# Motor_Driver_Card.net
KiCad netlist of a schematic drawn in EAGLE
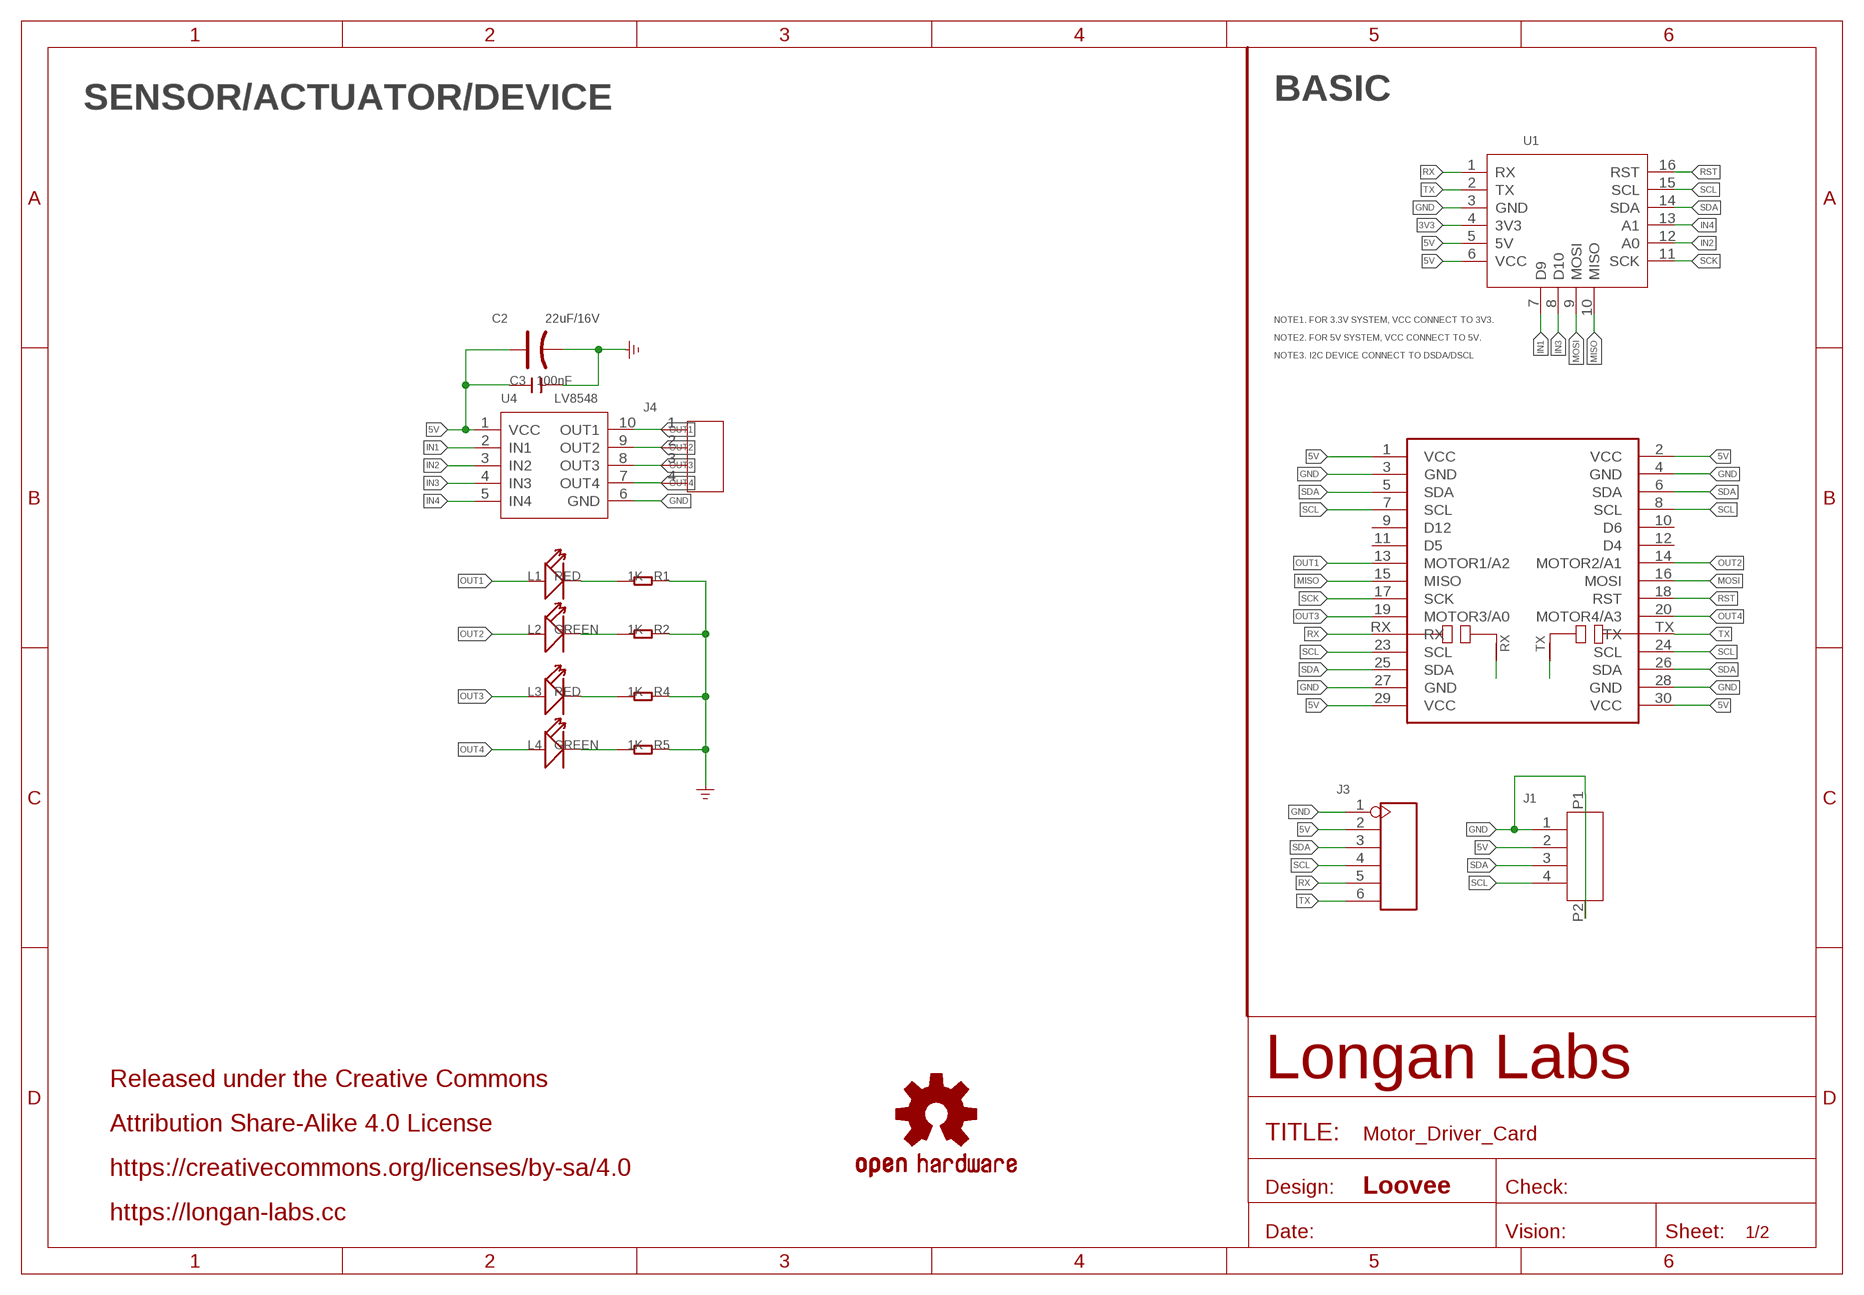
[diagram p0: schematic, sheet 1]

(export (version "E")
  (design (tool "Eeschema 10.0.6"))
  (components
    (comp (ref "C2")
      (value "22uF/16V")
      (footprint "eagle-import:AVX-A")
      (libsource (lib "eagle-import") (part "CAP-POLAR-AVX-A"))
    )
    (comp (ref "C3")
      (value "100nF")
      (footprint "eagle-import:C0603")
      (libsource (lib "eagle-import") (part "C-0603"))
    )
    (comp (ref "J1")
      (value "HEADER-4P-1.0")
      (footprint "eagle-import:4P-1.0-90D")
      (libsource (lib "eagle-import") (part "HEADER-4P-1.0"))
    )
    (comp (ref "J3")
      (value "HEADER-6P-55/35MIL")
      (footprint "eagle-import:H6-2.54")
      (libsource (lib "eagle-import") (part "HEADER-6P-55/35MIL"))
    )
    (comp (ref "J4")
      (value "SCREW-TERMINAL-4P'3.5'")
      (footprint "eagle-import:H4-3.5-14.0X7.0MM")
      (libsource (lib "eagle-import") (part "SCREW-TERMINAL-4P'3.5'"))
    )
    (comp (ref "L1")
      (value "RED")
      (footprint "eagle-import:LED-0603")
      (libsource (lib "eagle-import") (part "LED'0603'"))
    )
    (comp (ref "L2")
      (value "GREEN")
      (footprint "eagle-import:LED-0603")
      (libsource (lib "eagle-import") (part "LED'0603'"))
    )
    (comp (ref "L3")
      (value "RED")
      (footprint "eagle-import:LED-0603")
      (libsource (lib "eagle-import") (part "LED'0603'"))
    )
    (comp (ref "L4")
      (value "GREEN")
      (footprint "eagle-import:LED-0603")
      (libsource (lib "eagle-import") (part "LED'0603'"))
    )
    (comp (ref "LOGO2")
      (value "OSHW-LOGOS")
      (footprint "eagle-import:OSHW-LOGO-S")
      (libsource (lib "eagle-import") (part "OSHW-LOGOS"))
    )
    (comp (ref "MOUDLE2")
      (value "MOUDLE-CARDS-UART'BOARD'")
      (footprint "eagle-import:MOUDLE-2X15P-UART")
      (libsource (lib "eagle-import") (part "MOUDLE-CARDS-UART'BOARD'"))
    )
    (comp (ref "R1")
      (value "1K")
      (footprint "eagle-import:R0603")
      (libsource (lib "eagle-import") (part "R-0603"))
    )
    (comp (ref "R2")
      (value "1K")
      (footprint "eagle-import:R0603")
      (libsource (lib "eagle-import") (part "R-0603"))
    )
    (comp (ref "R4")
      (value "1K")
      (footprint "eagle-import:R0603")
      (libsource (lib "eagle-import") (part "R-0603"))
    )
    (comp (ref "R5")
      (value "1K")
      (footprint "eagle-import:R0603")
      (libsource (lib "eagle-import") (part "R-0603"))
    )
    (comp (ref "U1")
      (value "MOUDLE-CARDS")
      (footprint "eagle-import:16P-2.0-CARDS")
      (libsource (lib "eagle-import") (part "MOUDLE-CARDS"))
    )
    (comp (ref "U4")
      (value "LV8548")
      (footprint "eagle-import:SOIC10-1.0-5X4X1.5MM")
      (libsource (lib "eagle-import") (part "DRIVER-LV8548MC"))
    )
  )
  (nets
    (net (code "1") (name "3V3") (class "Default")
      (node (ref "U1") (pin "4") (pinfunction "3V3_4") (pintype "bidirectional"))
    )
    (net (code "2") (name "5V") (class "Default")
      (node (ref "C2") (pin "+") (pinfunction "+_+") (pintype "passive"))
      (node (ref "C3") (pin "1") (pinfunction "1_1") (pintype "passive"))
      (node (ref "J1") (pin "2") (pinfunction "2_2") (pintype "bidirectional"))
      (node (ref "J3") (pin "2") (pinfunction "2_2") (pintype "bidirectional"))
      (node (ref "MOUDLE2") (pin "1") (pinfunction "VCC_1") (pintype "bidirectional"))
      (node (ref "MOUDLE2") (pin "2") (pinfunction "VCC_2") (pintype "bidirectional"))
      (node (ref "MOUDLE2") (pin "29") (pinfunction "VCC_29") (pintype "bidirectional"))
      (node (ref "MOUDLE2") (pin "30") (pinfunction "VCC_30") (pintype "bidirectional"))
      (node (ref "U1") (pin "5") (pinfunction "5V_5") (pintype "bidirectional"))
      (node (ref "U1") (pin "6") (pinfunction "VCC_6") (pintype "bidirectional"))
      (node (ref "U4") (pin "1") (pinfunction "VCC_1") (pintype "bidirectional"))
    )
    (net (code "3") (name "GND") (class "Default")
      (node (ref "C2") (pin "-") (pinfunction "-_-") (pintype "passive"))
      (node (ref "C3") (pin "2") (pinfunction "2_2") (pintype "passive"))
      (node (ref "J1") (pin "1") (pinfunction "1_1") (pintype "bidirectional"))
      (node (ref "J1") (pin "P1") (pinfunction "P1_P1") (pintype "bidirectional"))
      (node (ref "J1") (pin "P2") (pinfunction "P2_P2") (pintype "bidirectional"))
      (node (ref "J3") (pin "1") (pinfunction "1_1") (pintype "bidirectional"))
      (node (ref "MOUDLE2") (pin "27") (pinfunction "GND_27") (pintype "bidirectional"))
      (node (ref "MOUDLE2") (pin "28") (pinfunction "GND_28") (pintype "bidirectional"))
      (node (ref "MOUDLE2") (pin "3") (pinfunction "GND_3") (pintype "bidirectional"))
      (node (ref "MOUDLE2") (pin "4") (pinfunction "GND_4") (pintype "bidirectional"))
      (node (ref "R1") (pin "1") (pinfunction "1_1") (pintype "passive"))
      (node (ref "R2") (pin "1") (pinfunction "1_1") (pintype "passive"))
      (node (ref "R4") (pin "1") (pinfunction "1_1") (pintype "passive"))
      (node (ref "R5") (pin "1") (pinfunction "1_1") (pintype "passive"))
      (node (ref "U1") (pin "3") (pinfunction "GND_3") (pintype "bidirectional"))
      (node (ref "U4") (pin "6") (pinfunction "GND_6") (pintype "bidirectional"))
    )
    (net (code "4") (name "IN1") (class "Default")
      (node (ref "U1") (pin "7") (pinfunction "D9_7") (pintype "bidirectional"))
      (node (ref "U4") (pin "2") (pinfunction "IN1_2") (pintype "bidirectional"))
    )
    (net (code "5") (name "IN2") (class "Default")
      (node (ref "U1") (pin "12") (pinfunction "A0_12") (pintype "bidirectional"))
      (node (ref "U4") (pin "3") (pinfunction "IN2_3") (pintype "bidirectional"))
    )
    (net (code "6") (name "IN3") (class "Default")
      (node (ref "U1") (pin "8") (pinfunction "D10_8") (pintype "bidirectional"))
      (node (ref "U4") (pin "4") (pinfunction "IN3_4") (pintype "bidirectional"))
    )
    (net (code "7") (name "IN4") (class "Default")
      (node (ref "U1") (pin "13") (pinfunction "A1_13") (pintype "bidirectional"))
      (node (ref "U4") (pin "5") (pinfunction "IN4_5") (pintype "bidirectional"))
    )
    (net (code "8") (name "MISO") (class "Default")
      (node (ref "MOUDLE2") (pin "15") (pinfunction "MISO_15") (pintype "bidirectional"))
      (node (ref "U1") (pin "10") (pinfunction "MISO_10") (pintype "bidirectional"))
    )
    (net (code "9") (name "MOSI") (class "Default")
      (node (ref "MOUDLE2") (pin "16") (pinfunction "MOSI_16") (pintype "bidirectional"))
      (node (ref "U1") (pin "9") (pinfunction "MOSI_9") (pintype "bidirectional"))
    )
    (net (code "10") (name "Net-(L1-Pad-)") (class "Default")
      (node (ref "L1") (pin "-") (pinfunction "-_-") (pintype "passive"))
      (node (ref "R1") (pin "2") (pinfunction "2_2") (pintype "passive"))
    )
    (net (code "11") (name "Net-(L2-Pad-)") (class "Default")
      (node (ref "L2") (pin "-") (pinfunction "-_-") (pintype "passive"))
      (node (ref "R2") (pin "2") (pinfunction "2_2") (pintype "passive"))
    )
    (net (code "12") (name "Net-(L3-Pad-)") (class "Default")
      (node (ref "L3") (pin "-") (pinfunction "-_-") (pintype "passive"))
      (node (ref "R4") (pin "2") (pinfunction "2_2") (pintype "passive"))
    )
    (net (code "13") (name "Net-(L4-Pad-)") (class "Default")
      (node (ref "L4") (pin "-") (pinfunction "-_-") (pintype "passive"))
      (node (ref "R5") (pin "2") (pinfunction "2_2") (pintype "passive"))
    )
    (net (code "14") (name "Net-(MOUDLE2-RX{slash}N-PadRX{slash}N1)") (class "Default")
      (node (ref "MOUDLE2") (pin "RX/N1") (pinfunction "RX/N_RX/N1") (pintype "bidirectional"))
      (node (ref "MOUDLE2") (pin "RX/N2") (pinfunction "RX/N_RX/N2") (pintype "bidirectional"))
    )
    (net (code "15") (name "Net-(MOUDLE2-TX{slash}N-PadTX{slash}N1)") (class "Default")
      (node (ref "MOUDLE2") (pin "TX/N1") (pinfunction "TX/N_TX/N1") (pintype "bidirectional"))
      (node (ref "MOUDLE2") (pin "TX/N2") (pinfunction "TX/N_TX/N2") (pintype "bidirectional"))
    )
    (net (code "16") (name "OUT1") (class "Default")
      (node (ref "J4") (pin "1") (pinfunction "1_1") (pintype "bidirectional"))
      (node (ref "L1") (pin "+") (pinfunction "+_+") (pintype "passive"))
      (node (ref "MOUDLE2") (pin "13") (pinfunction "MOTOR1/A2_13") (pintype "bidirectional"))
      (node (ref "U4") (pin "10") (pinfunction "OUT1_10") (pintype "bidirectional"))
    )
    (net (code "17") (name "OUT2") (class "Default")
      (node (ref "J4") (pin "2") (pinfunction "2_2") (pintype "bidirectional"))
      (node (ref "L2") (pin "+") (pinfunction "+_+") (pintype "passive"))
      (node (ref "MOUDLE2") (pin "14") (pinfunction "MOTOR2/A1_14") (pintype "bidirectional"))
      (node (ref "U4") (pin "9") (pinfunction "OUT2_9") (pintype "bidirectional"))
    )
    (net (code "18") (name "OUT3") (class "Default")
      (node (ref "J4") (pin "3") (pinfunction "3_3") (pintype "bidirectional"))
      (node (ref "L3") (pin "+") (pinfunction "+_+") (pintype "passive"))
      (node (ref "MOUDLE2") (pin "19") (pinfunction "MOTOR3/A0_19") (pintype "bidirectional"))
      (node (ref "U4") (pin "8") (pinfunction "OUT3_8") (pintype "bidirectional"))
    )
    (net (code "19") (name "OUT4") (class "Default")
      (node (ref "J4") (pin "4") (pinfunction "4_4") (pintype "bidirectional"))
      (node (ref "L4") (pin "+") (pinfunction "+_+") (pintype "passive"))
      (node (ref "MOUDLE2") (pin "20") (pinfunction "MOTOR4/A3_20") (pintype "bidirectional"))
      (node (ref "U4") (pin "7") (pinfunction "OUT4_7") (pintype "bidirectional"))
    )
    (net (code "20") (name "RST") (class "Default")
      (node (ref "MOUDLE2") (pin "18") (pinfunction "RST_18") (pintype "bidirectional"))
      (node (ref "U1") (pin "16") (pinfunction "RST_16") (pintype "bidirectional"))
    )
    (net (code "21") (name "RX") (class "Default")
      (node (ref "J3") (pin "5") (pinfunction "5_5") (pintype "bidirectional"))
      (node (ref "MOUDLE2") (pin "RX") (pinfunction "RX_RX") (pintype "bidirectional"))
      (node (ref "U1") (pin "1") (pinfunction "RX_1") (pintype "bidirectional"))
    )
    (net (code "22") (name "SCK") (class "Default")
      (node (ref "MOUDLE2") (pin "17") (pinfunction "SCK_17") (pintype "bidirectional"))
      (node (ref "U1") (pin "11") (pinfunction "SCK_11") (pintype "bidirectional"))
    )
    (net (code "23") (name "SCL") (class "Default")
      (node (ref "J1") (pin "4") (pinfunction "4_4") (pintype "bidirectional"))
      (node (ref "J3") (pin "4") (pinfunction "4_4") (pintype "bidirectional"))
      (node (ref "MOUDLE2") (pin "23") (pinfunction "SCL_23") (pintype "bidirectional"))
      (node (ref "MOUDLE2") (pin "24") (pinfunction "SCL_24") (pintype "bidirectional"))
      (node (ref "MOUDLE2") (pin "7") (pinfunction "SCL_7") (pintype "bidirectional"))
      (node (ref "MOUDLE2") (pin "8") (pinfunction "SCL_8") (pintype "bidirectional"))
      (node (ref "U1") (pin "15") (pinfunction "SCL_15") (pintype "bidirectional"))
    )
    (net (code "24") (name "SDA") (class "Default")
      (node (ref "J1") (pin "3") (pinfunction "3_3") (pintype "bidirectional"))
      (node (ref "J3") (pin "3") (pinfunction "3_3") (pintype "bidirectional"))
      (node (ref "MOUDLE2") (pin "25") (pinfunction "SDA_25") (pintype "bidirectional"))
      (node (ref "MOUDLE2") (pin "26") (pinfunction "SDA_26") (pintype "bidirectional"))
      (node (ref "MOUDLE2") (pin "5") (pinfunction "SDA_5") (pintype "bidirectional"))
      (node (ref "MOUDLE2") (pin "6") (pinfunction "SDA_6") (pintype "bidirectional"))
      (node (ref "U1") (pin "14") (pinfunction "SDA_14") (pintype "bidirectional"))
    )
    (net (code "25") (name "TX") (class "Default")
      (node (ref "J3") (pin "6") (pinfunction "6_6") (pintype "bidirectional"))
      (node (ref "MOUDLE2") (pin "TX") (pinfunction "TX_TX") (pintype "bidirectional"))
      (node (ref "U1") (pin "2") (pinfunction "TX_2") (pintype "bidirectional"))
    )
    (net (code "26") (name "unconnected-(MOUDLE2-D4-Pad12)") (class "Default")
      (node (ref "MOUDLE2") (pin "12") (pinfunction "D4_12") (pintype "bidirectional"))
    )
    (net (code "27") (name "unconnected-(MOUDLE2-D5-Pad11)") (class "Default")
      (node (ref "MOUDLE2") (pin "11") (pinfunction "D5_11") (pintype "bidirectional"))
    )
    (net (code "28") (name "unconnected-(MOUDLE2-D6-Pad10)") (class "Default")
      (node (ref "MOUDLE2") (pin "10") (pinfunction "D6_10") (pintype "bidirectional"))
    )
    (net (code "29") (name "unconnected-(MOUDLE2-D12-Pad9)") (class "Default")
      (node (ref "MOUDLE2") (pin "9") (pinfunction "D12_9") (pintype "bidirectional"))
    )
  )
)
